# 8051.net
KiCad netlist of a schematic drawn in Altium Designer
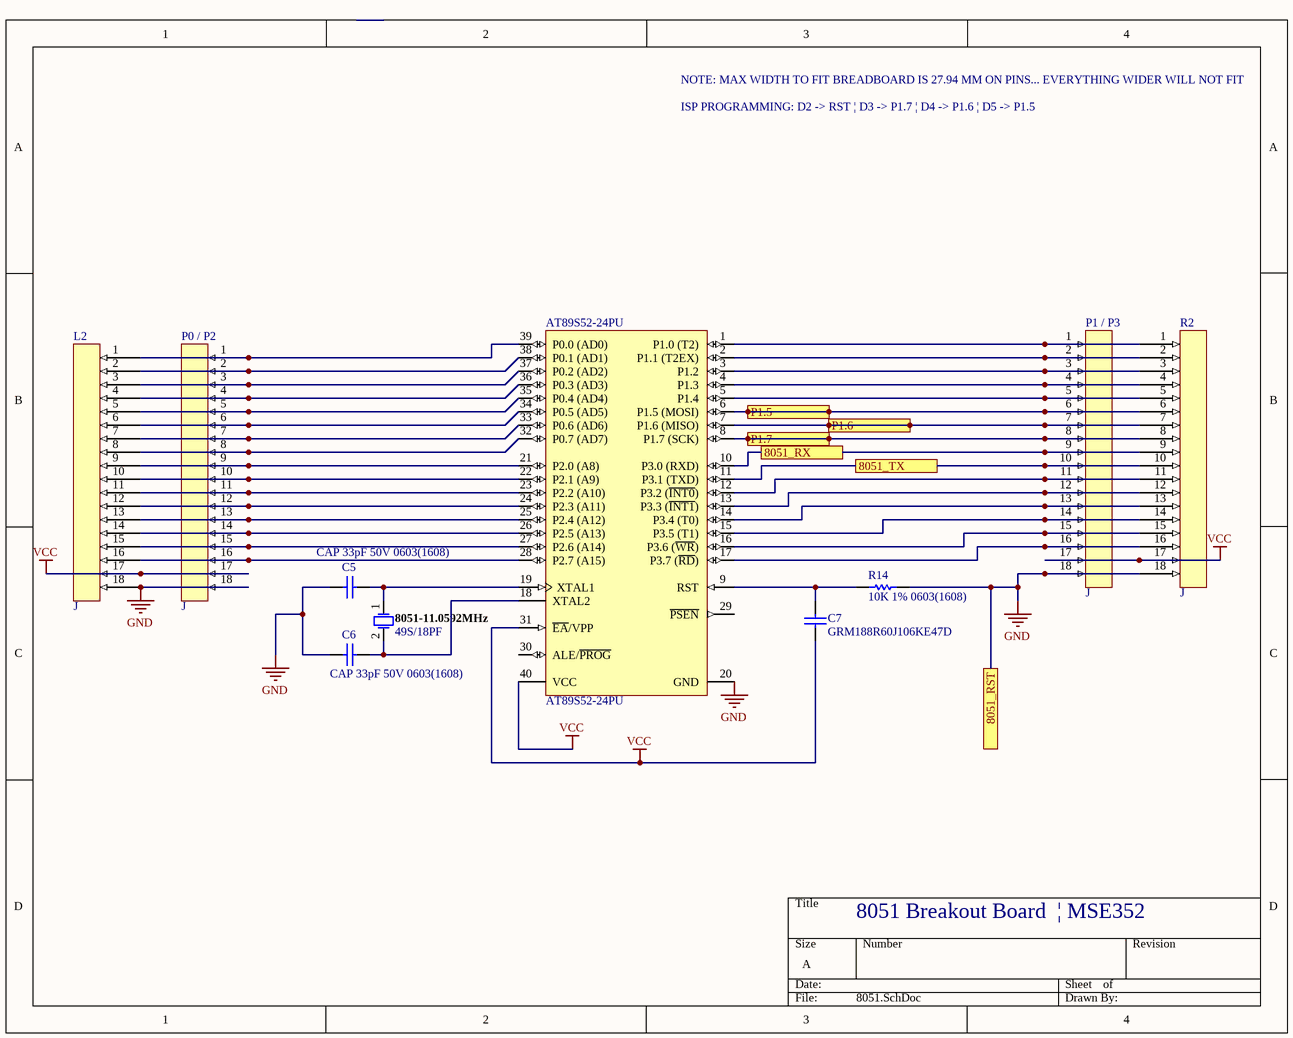
[diagram p0: 8051.SchDoc]

(export (version "E")
  (design (tool "Eeschema 10.0.6"))
  (components
    (comp (ref "8051-11.0592MHz")
      (value "49S/18PF")
      (footprint "JPY-49S-18PF")
      (description "Crystal, 16 MHz, 18 pF, -20 to 70 degC, 2-Pin THD")
      (fields (field (name "MANUFACTURER") "Shenzhen Jingpengyuan"))
      (libsource (lib "Altium Content Vault") (part "XTAL-1-2-2"))
    )
    (comp (ref "AT89S52-24PU")
      (value "AT89S52-24PU")
      (footprint "ATML-40P6")
      (fields (field (name "MANUFACTURER") "Microchip"))
      (libsource (lib "Altium Content Vault") (part "ATML-AT89S52-40P6"))
    )
    (comp (ref "C5")
      (value "CAP 33pF 50V 0603(1608)")
      (footprint "CAPC0603(1608)100_L")
      (description "CAP 33pF 50V ±2% 0603 (1608 Metric) Thickness 1mm SMD")
      (fields (field (name "TOLERANCE") "Â±2%"))
      (libsource (lib "Altium Content Vault") (part "CAP"))
    )
    (comp (ref "C6")
      (value "CAP 33pF 50V 0603(1608)")
      (footprint "CAPC0603(1608)100_L")
      (description "CAP 33pF 50V ±2% 0603 (1608 Metric) Thickness 1mm SMD")
      (fields (field (name "TOLERANCE") "Â±2%"))
      (libsource (lib "Altium Content Vault") (part "CAP"))
    )
    (comp (ref "C7")
      (value "GRM188R60J106KE47D")
      (footprint "CAPC1608X90X38LL10T18")
      (description "Chip Capacitor, 10 uF, +/- 10%, 6.3 V, -55 to 85 degC, 0603 (1608 Metric), RoHS, Tape and Reel")
      (fields (field (name "MANUFACTURER") "Murata") (field (name "TOLERANCE") "10%"))
      (libsource (lib "Altium Content Vault") (part "CAP-NP-2"))
    )
    (comp (ref "L2") (value "J") (footprint "16 pin holes") (libsource (lib "8051mk3") (part "16 pin holes")))
    (comp (ref "P0 / P2")
      (value "J")
      (footprint "16 pin holes")
      (libsource (lib "8051mk3") (part "16 pin holes"))
    )
    (comp (ref "P1 / P3") (value "J") (footprint "16 pin holes") (libsource (lib "") (part "16 pin holes_1")))
    (comp (ref "R2") (value "J") (footprint "16 pin holes") (libsource (lib "") (part "16 pin holes_1")))
    (comp (ref "R14")
      (value "10K 1% 0603(1608)")
      (footprint "RESC0603(1608)_N")
      (description "10K 0.1W 1% 0603 (1608 Metric)  SMD")
      (fields (field (name "POWER") "0.1 W") (field (name "TOLERANCE") "1 %"))
      (libsource (lib "Altium Content Vault") (part "RES"))
    )
  )
  (nets
    (net (code "1") (name "/8051_RX") (class "Default")
      (node (ref "AT89S52-24PU") (pin "10") (pinfunction "P3.0_(RXD)_10") (pintype "bidirectional"))
      (node (ref "P1 / P3") (pin "9") (pintype "input"))
      (node (ref "R2") (pin "9") (pintype "input"))
    )
    (net (code "2") (name "/8051_TX") (class "Default")
      (node (ref "AT89S52-24PU") (pin "11") (pinfunction "P3.1_(TXD)_11") (pintype "bidirectional"))
      (node (ref "P1 / P3") (pin "10") (pintype "input"))
      (node (ref "R2") (pin "10") (pintype "input"))
    )
    (net (code "3") (name "/P1.5") (class "Default")
      (node (ref "AT89S52-24PU") (pin "6") (pinfunction "P1.5_(MOSI)_6") (pintype "bidirectional"))
      (node (ref "P1 / P3") (pin "6") (pintype "input"))
      (node (ref "R2") (pin "6") (pintype "input"))
    )
    (net (code "4") (name "/P1.6") (class "Default")
      (node (ref "AT89S52-24PU") (pin "7") (pinfunction "P1.6_(MISO)_7") (pintype "bidirectional"))
      (node (ref "P1 / P3") (pin "7") (pintype "input"))
      (node (ref "R2") (pin "7") (pintype "input"))
    )
    (net (code "5") (name "/P1.7") (class "Default")
      (node (ref "AT89S52-24PU") (pin "8") (pinfunction "P1.7_(SCK)_8") (pintype "bidirectional"))
      (node (ref "P1 / P3") (pin "8") (pintype "input"))
      (node (ref "R2") (pin "8") (pintype "input"))
    )
    (net (code "6") (name "GND") (class "Default")
      (node (ref "AT89S52-24PU") (pin "20") (pinfunction "GND_20") (pintype "power_in"))
      (node (ref "C5") (pin "1") (pinfunction "1_1") (pintype "passive"))
      (node (ref "C6") (pin "1") (pinfunction "1_1") (pintype "passive"))
      (node (ref "L2") (pin "18") (pintype "input"))
      (node (ref "P0 / P2") (pin "18") (pintype "input"))
      (node (ref "P1 / P3") (pin "18") (pintype "input"))
      (node (ref "R14") (pin "2") (pinfunction "2_2") (pintype "passive"))
      (node (ref "R2") (pin "18") (pintype "input"))
    )
    (net (code "7") (name "Net-(AT89S52-24PU-P0.0_(AD0))") (class "Default")
      (node (ref "AT89S52-24PU") (pin "39") (pinfunction "P0.0_(AD0)_39") (pintype "bidirectional"))
      (node (ref "L2") (pin "1") (pintype "input"))
      (node (ref "P0 / P2") (pin "1") (pintype "input"))
    )
    (net (code "8") (name "Net-(AT89S52-24PU-P0.1_(AD1))") (class "Default")
      (node (ref "AT89S52-24PU") (pin "38") (pinfunction "P0.1_(AD1)_38") (pintype "bidirectional"))
      (node (ref "L2") (pin "2") (pintype "input"))
      (node (ref "P0 / P2") (pin "2") (pintype "input"))
    )
    (net (code "9") (name "Net-(AT89S52-24PU-P0.2_(AD2))") (class "Default")
      (node (ref "AT89S52-24PU") (pin "37") (pinfunction "P0.2_(AD2)_37") (pintype "bidirectional"))
      (node (ref "L2") (pin "3") (pintype "input"))
      (node (ref "P0 / P2") (pin "3") (pintype "input"))
    )
    (net (code "10") (name "Net-(AT89S52-24PU-P0.3_(AD3))") (class "Default")
      (node (ref "AT89S52-24PU") (pin "36") (pinfunction "P0.3_(AD3)_36") (pintype "bidirectional"))
      (node (ref "L2") (pin "4") (pintype "input"))
      (node (ref "P0 / P2") (pin "4") (pintype "input"))
    )
    (net (code "11") (name "Net-(AT89S52-24PU-P0.4_(AD4))") (class "Default")
      (node (ref "AT89S52-24PU") (pin "35") (pinfunction "P0.4_(AD4)_35") (pintype "bidirectional"))
      (node (ref "L2") (pin "5") (pintype "input"))
      (node (ref "P0 / P2") (pin "5") (pintype "input"))
    )
    (net (code "12") (name "Net-(AT89S52-24PU-P0.5_(AD5))") (class "Default")
      (node (ref "AT89S52-24PU") (pin "34") (pinfunction "P0.5_(AD5)_34") (pintype "bidirectional"))
      (node (ref "L2") (pin "6") (pintype "input"))
      (node (ref "P0 / P2") (pin "6") (pintype "input"))
    )
    (net (code "13") (name "Net-(AT89S52-24PU-P0.6_(AD6))") (class "Default")
      (node (ref "AT89S52-24PU") (pin "33") (pinfunction "P0.6_(AD6)_33") (pintype "bidirectional"))
      (node (ref "L2") (pin "7") (pintype "input"))
      (node (ref "P0 / P2") (pin "7") (pintype "input"))
    )
    (net (code "14") (name "Net-(AT89S52-24PU-P0.7_(AD7))") (class "Default")
      (node (ref "AT89S52-24PU") (pin "32") (pinfunction "P0.7_(AD7)_32") (pintype "bidirectional"))
      (node (ref "L2") (pin "8") (pintype "input"))
      (node (ref "P0 / P2") (pin "8") (pintype "input"))
    )
    (net (code "15") (name "Net-(AT89S52-24PU-P1.0_(T2))") (class "Default")
      (node (ref "AT89S52-24PU") (pin "1") (pinfunction "P1.0_(T2)_1") (pintype "bidirectional"))
      (node (ref "P1 / P3") (pin "1") (pintype "input"))
      (node (ref "R2") (pin "1") (pintype "input"))
    )
    (net (code "16") (name "Net-(AT89S52-24PU-P1.1_(T2EX))") (class "Default")
      (node (ref "AT89S52-24PU") (pin "2") (pinfunction "P1.1_(T2EX)_2") (pintype "bidirectional"))
      (node (ref "P1 / P3") (pin "2") (pintype "input"))
      (node (ref "R2") (pin "2") (pintype "input"))
    )
    (net (code "17") (name "Net-(AT89S52-24PU-P1.2)") (class "Default")
      (node (ref "AT89S52-24PU") (pin "3") (pinfunction "P1.2_3") (pintype "bidirectional"))
      (node (ref "P1 / P3") (pin "3") (pintype "input"))
      (node (ref "R2") (pin "3") (pintype "input"))
    )
    (net (code "18") (name "Net-(AT89S52-24PU-P1.3)") (class "Default")
      (node (ref "AT89S52-24PU") (pin "4") (pinfunction "P1.3_4") (pintype "bidirectional"))
      (node (ref "P1 / P3") (pin "4") (pintype "input"))
      (node (ref "R2") (pin "4") (pintype "input"))
    )
    (net (code "19") (name "Net-(AT89S52-24PU-P1.4)") (class "Default")
      (node (ref "AT89S52-24PU") (pin "5") (pinfunction "P1.4_5") (pintype "bidirectional"))
      (node (ref "P1 / P3") (pin "5") (pintype "input"))
      (node (ref "R2") (pin "5") (pintype "input"))
    )
    (net (code "20") (name "Net-(AT89S52-24PU-P2.0_(A8))") (class "Default")
      (node (ref "AT89S52-24PU") (pin "21") (pinfunction "P2.0_(A8)_21") (pintype "bidirectional"))
      (node (ref "L2") (pin "9") (pintype "input"))
      (node (ref "P0 / P2") (pin "9") (pintype "input"))
    )
    (net (code "21") (name "Net-(AT89S52-24PU-P2.1_(A9))") (class "Default")
      (node (ref "AT89S52-24PU") (pin "22") (pinfunction "P2.1_(A9)_22") (pintype "bidirectional"))
      (node (ref "L2") (pin "10") (pintype "input"))
      (node (ref "P0 / P2") (pin "10") (pintype "input"))
    )
    (net (code "22") (name "Net-(AT89S52-24PU-P2.2_(A10))") (class "Default")
      (node (ref "AT89S52-24PU") (pin "23") (pinfunction "P2.2_(A10)_23") (pintype "bidirectional"))
      (node (ref "L2") (pin "11") (pintype "input"))
      (node (ref "P0 / P2") (pin "11") (pintype "input"))
    )
    (net (code "23") (name "Net-(AT89S52-24PU-P2.3_(A11))") (class "Default")
      (node (ref "AT89S52-24PU") (pin "24") (pinfunction "P2.3_(A11)_24") (pintype "bidirectional"))
      (node (ref "L2") (pin "12") (pintype "input"))
      (node (ref "P0 / P2") (pin "12") (pintype "input"))
    )
    (net (code "24") (name "Net-(AT89S52-24PU-P2.4_(A12))") (class "Default")
      (node (ref "AT89S52-24PU") (pin "25") (pinfunction "P2.4_(A12)_25") (pintype "bidirectional"))
      (node (ref "L2") (pin "13") (pintype "input"))
      (node (ref "P0 / P2") (pin "13") (pintype "input"))
    )
    (net (code "25") (name "Net-(AT89S52-24PU-P2.5_(A13))") (class "Default")
      (node (ref "AT89S52-24PU") (pin "26") (pinfunction "P2.5_(A13)_26") (pintype "bidirectional"))
      (node (ref "L2") (pin "14") (pintype "input"))
      (node (ref "P0 / P2") (pin "14") (pintype "input"))
    )
    (net (code "26") (name "Net-(AT89S52-24PU-P2.6_(A14))") (class "Default")
      (node (ref "AT89S52-24PU") (pin "27") (pinfunction "P2.6_(A14)_27") (pintype "bidirectional"))
      (node (ref "L2") (pin "15") (pintype "input"))
      (node (ref "P0 / P2") (pin "15") (pintype "input"))
    )
    (net (code "27") (name "Net-(AT89S52-24PU-P2.7_(A15))") (class "Default")
      (node (ref "AT89S52-24PU") (pin "28") (pinfunction "P2.7_(A15)_28") (pintype "bidirectional"))
      (node (ref "L2") (pin "16") (pintype "input"))
      (node (ref "P0 / P2") (pin "16") (pintype "input"))
    )
    (net (code "28") (name "Net-(AT89S52-24PU-P3.2_(~{INT0}))") (class "Default")
      (node (ref "AT89S52-24PU") (pin "12") (pinfunction "P3.2_(~{INT0})_12") (pintype "bidirectional"))
      (node (ref "P1 / P3") (pin "11") (pintype "input"))
      (node (ref "R2") (pin "11") (pintype "input"))
    )
    (net (code "29") (name "Net-(AT89S52-24PU-P3.3_(~{INT1}))") (class "Default")
      (node (ref "AT89S52-24PU") (pin "13") (pinfunction "P3.3_(~{INT1})_13") (pintype "bidirectional"))
      (node (ref "P1 / P3") (pin "12") (pintype "input"))
      (node (ref "R2") (pin "12") (pintype "input"))
    )
    (net (code "30") (name "Net-(AT89S52-24PU-P3.4_(T0))") (class "Default")
      (node (ref "AT89S52-24PU") (pin "14") (pinfunction "P3.4_(T0)_14") (pintype "bidirectional"))
      (node (ref "P1 / P3") (pin "13") (pintype "input"))
      (node (ref "R2") (pin "13") (pintype "input"))
    )
    (net (code "31") (name "Net-(AT89S52-24PU-P3.5_(T1))") (class "Default")
      (node (ref "AT89S52-24PU") (pin "15") (pinfunction "P3.5_(T1)_15") (pintype "bidirectional"))
      (node (ref "P1 / P3") (pin "14") (pintype "input"))
      (node (ref "R2") (pin "14") (pintype "input"))
    )
    (net (code "32") (name "Net-(AT89S52-24PU-P3.6_(~{WR}))") (class "Default")
      (node (ref "AT89S52-24PU") (pin "16") (pinfunction "P3.6_(~{WR})_16") (pintype "bidirectional"))
      (node (ref "P1 / P3") (pin "15") (pintype "input"))
      (node (ref "R2") (pin "15") (pintype "input"))
    )
    (net (code "33") (name "Net-(AT89S52-24PU-P3.7_(~{RD}))") (class "Default")
      (node (ref "AT89S52-24PU") (pin "17") (pinfunction "P3.7_(~{RD})_17") (pintype "bidirectional"))
      (node (ref "P1 / P3") (pin "16") (pintype "input"))
      (node (ref "R2") (pin "16") (pintype "input"))
    )
    (net (code "34") (name "Net-(AT89S52-24PU-RST)") (class "Default")
      (node (ref "AT89S52-24PU") (pin "9") (pinfunction "RST_9") (pintype "input"))
      (node (ref "C7") (pin "2") (pinfunction "2_2") (pintype "passive"))
      (node (ref "R14") (pin "1") (pinfunction "1_1") (pintype "passive"))
    )
    (net (code "35") (name "Net-(AT89S52-24PU-XTAL1)") (class "Default")
      (node (ref "8051-11.0592MHz") (pin "1") (pinfunction "1_1") (pintype "passive"))
      (node (ref "AT89S52-24PU") (pin "19") (pinfunction "XTAL1_19") (pintype "input"))
      (node (ref "C5") (pin "2") (pinfunction "2_2") (pintype "passive"))
    )
    (net (code "36") (name "Net-(AT89S52-24PU-XTAL2)") (class "Default")
      (node (ref "8051-11.0592MHz") (pin "2") (pinfunction "2_2") (pintype "passive"))
      (node (ref "AT89S52-24PU") (pin "18") (pinfunction "XTAL2_18") (pintype "passive"))
      (node (ref "C6") (pin "2") (pinfunction "2_2") (pintype "passive"))
    )
    (net (code "37") (name "VCC") (class "Default")
      (node (ref "AT89S52-24PU") (pin "31") (pinfunction "~{EA}/VPP_31") (pintype "input"))
      (node (ref "AT89S52-24PU") (pin "40") (pinfunction "VCC_40") (pintype "power_in"))
      (node (ref "C7") (pin "1") (pinfunction "1_1") (pintype "passive"))
      (node (ref "L2") (pin "17") (pintype "input"))
      (node (ref "P0 / P2") (pin "17") (pintype "input"))
      (node (ref "P1 / P3") (pin "17") (pintype "input"))
      (node (ref "R2") (pin "17") (pintype "input"))
    )
    (net (code "38") (name "unconnected-(AT89S52-24PU-ALE{slash}~{PROG}-Pad30)") (class "Default")
      (node (ref "AT89S52-24PU") (pin "30") (pinfunction "ALE/~{PROG}_30") (pintype "bidirectional"))
    )
    (net (code "39") (name "unconnected-(AT89S52-24PU-~{PSEN}-Pad29)") (class "Default")
      (node (ref "AT89S52-24PU") (pin "29") (pinfunction "~{PSEN}_29") (pintype "output"))
    )
  )
)
